# sensor-dual.net
KiCad netlist of a schematic drawn in EAGLE
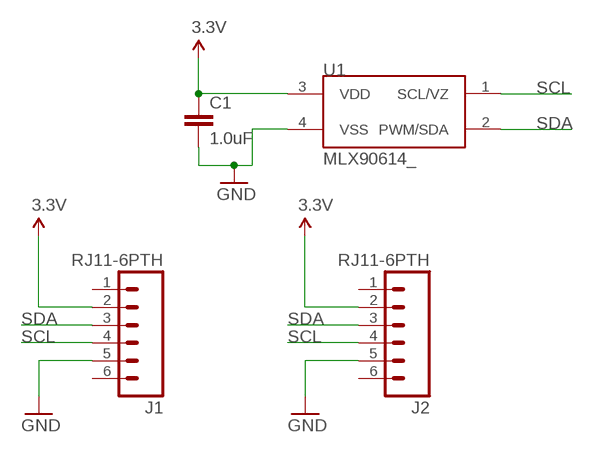
[diagram p0: schematic, sheet 1]

(export (version "E")
  (design (tool "Eeschema 10.0.6"))
  (components
    (comp (ref "C1")
      (value "1.0uF")
      (footprint "eagle-import:0805")
      (libsource (lib "eagle-import") (part "1.0UF-25V-+80/-20(0805)"))
    )
    (comp (ref "J1")
      (value "RJ11-6PTH")
      (footprint "eagle-import:RJ11-6")
      (libsource (lib "eagle-import") (part "RJ11-6PTH"))
    )
    (comp (ref "J2")
      (value "RJ11-6PTH")
      (footprint "eagle-import:RJ11-6")
      (libsource (lib "eagle-import") (part "RJ11-6PTH"))
    )
    (comp (ref "U1")
      (value "MLX90614_")
      (footprint "eagle-import:TO-39")
      (libsource (lib "eagle-import") (part "MLX90614_"))
    )
  )
  (nets
    (net (code "1") (name "/SCL") (class "Default")
      (node (ref "J1") (pin "4") (pinfunction "4_4") (pintype "passive"))
      (node (ref "J2") (pin "4") (pinfunction "4_4") (pintype "passive"))
      (node (ref "U1") (pin "1") (pinfunction "SCL/VZ_1") (pintype "bidirectional"))
    )
    (net (code "2") (name "/SDA") (class "Default")
      (node (ref "J1") (pin "3") (pinfunction "3_3") (pintype "passive"))
      (node (ref "J2") (pin "3") (pinfunction "3_3") (pintype "passive"))
      (node (ref "U1") (pin "2") (pinfunction "PWM/SDA_2") (pintype "bidirectional"))
    )
    (net (code "3") (name "3.3V") (class "Default")
      (node (ref "C1") (pin "1") (pinfunction "1_1") (pintype "passive"))
      (node (ref "J1") (pin "2") (pinfunction "2_2") (pintype "passive"))
      (node (ref "J2") (pin "2") (pinfunction "2_2") (pintype "passive"))
      (node (ref "U1") (pin "3") (pinfunction "VDD_3") (pintype "bidirectional"))
    )
    (net (code "4") (name "GND") (class "Default")
      (node (ref "C1") (pin "2") (pinfunction "2_2") (pintype "passive"))
      (node (ref "J1") (pin "5") (pinfunction "5_5") (pintype "passive"))
      (node (ref "J2") (pin "5") (pinfunction "5_5") (pintype "passive"))
      (node (ref "U1") (pin "4") (pinfunction "VSS_4") (pintype "bidirectional"))
    )
    (net (code "5") (name "unconnected-(J1-Pad1)") (class "Default")
      (node (ref "J1") (pin "1") (pinfunction "1_1") (pintype "passive"))
    )
    (net (code "6") (name "unconnected-(J1-Pad6)") (class "Default")
      (node (ref "J1") (pin "6") (pinfunction "6_6") (pintype "passive"))
    )
    (net (code "7") (name "unconnected-(J2-Pad1)") (class "Default")
      (node (ref "J2") (pin "1") (pinfunction "1_1") (pintype "passive"))
    )
    (net (code "8") (name "unconnected-(J2-Pad6)") (class "Default")
      (node (ref "J2") (pin "6") (pinfunction "6_6") (pintype "passive"))
    )
  )
)
